# bOOST_cONVERTER_var_2.net
KiCad netlist of a schematic drawn in Altium Designer
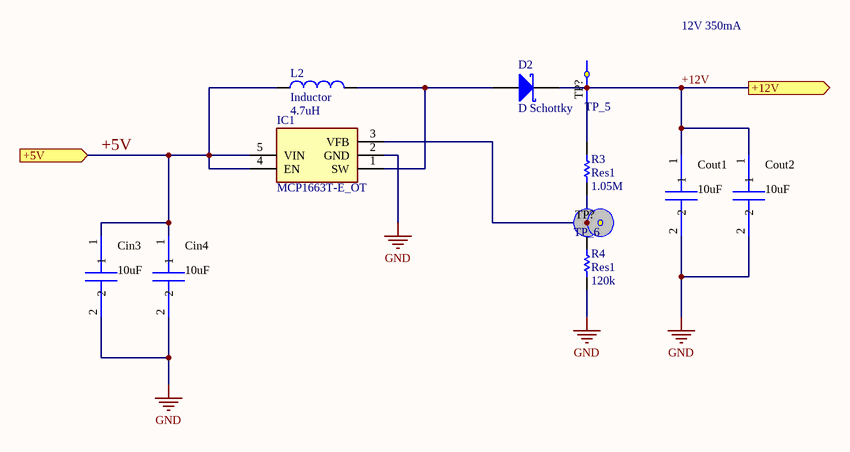
[diagram p0: bOOST cONVERTER_var 2.SchDoc]

(export (version "E")
  (design (tool "Eeschema 10.0.6"))
  (components
    (comp (ref "Cin3")
      (value "10uF")
      (description "C3216X6S1V106K16")
      (fields (field (name "MANUFACTURER PART NUMBER") "C3216X6S1V106K160AC"))
      (libsource (lib "TI WEBENCH") (part "Cin"))
    )
    (comp (ref "Cin4")
      (value "10uF")
      (description "C3216X6S1V106K16")
      (fields (field (name "MANUFACTURER PART NUMBER") "C3216X6S1V106K160AC"))
      (libsource (lib "TI WEBENCH") (part "Cin"))
    )
    (comp (ref "Cout1")
      (value "10uF")
      (description "C3216X6S1V106K16")
      (fields (field (name "MANUFACTURER PART NUMBER") "C3216X6S1V106K160AC"))
      (libsource (lib "TI WEBENCH") (part "Cin"))
    )
    (comp (ref "Cout2")
      (value "10uF")
      (description "C3216X6S1V106K16")
      (fields (field (name "MANUFACTURER PART NUMBER") "C3216X6S1V106K160AC"))
      (libsource (lib "TI WEBENCH") (part "Cin"))
    )
    (comp (ref "D2")
      (value "D Schottky")
      (footprint "SMB")
      (description "Schottky Diode")
      (fields (field (name "PUBLISHER") "Altium Limited"))
      (libsource (lib "Miscellaneous Devices") (part "D Schottky"))
    )
    (comp (ref "IC1")
      (value "MCP1663T-E_OT")
      (footprint "SamacSys:SOT95P270X145-5N")
      (description "Integrated Circuit")
      (fields
        (field (name "MANUFACTURER_PART_NUMBER") "MCP1663T-E/OT")
        (field (name "MOUSER PART NUMBER") "579-MCP1663T-E/OT")
      )
      (libsource (lib "*") (part "MCP1663T-E_OT"))
    )
    (comp (ref "L2")
      (value "Inductor")
      (footprint "0402-A")
      (fields (field (name "ALTIUM_VALUE") "4.7uH") (field (name "PUBLISHER") "Altium Limited"))
      (libsource (lib "Miscellaneous Devices") (part "Inductor"))
    )
    (comp (ref "R3")
      (value "Res1")
      (footprint "AXIAL-0.3")
      (description "Resistor")
      (fields (field (name "ALTIUM_VALUE") "1.05M") (field (name "PUBLISHER") "Altium Limited"))
      (libsource (lib "Miscellaneous Devices") (part "Res1"))
    )
    (comp (ref "R4")
      (value "Res1")
      (footprint "AXIAL-0.3")
      (description "Resistor")
      (fields (field (name "ALTIUM_VALUE") "120k") (field (name "PUBLISHER") "Altium Limited"))
      (libsource (lib "Miscellaneous Devices") (part "Res1"))
    )
    (comp (ref "TP_5")
      (value "Test_point")
      (footprint "PCBComponent_1")
      (description "Test_Point")
      (libsource (lib "") (part "Test_point_1"))
    )
    (comp (ref "TP_6")
      (value "Test_point")
      (footprint "PCBComponent_1")
      (description "Test_Point")
      (libsource (lib "Test_pointbun") (part "Test_point"))
    )
  )
  (nets
    (net (code "1") (name "/+5V") (class "Default")
      (node (ref "Cin3") (pin "1") (pinfunction "1_1") (pintype "passive"))
      (node (ref "Cin4") (pin "1") (pinfunction "1_1") (pintype "passive"))
      (node (ref "IC1") (pin "4") (pinfunction "EN_4") (pintype "passive"))
      (node (ref "IC1") (pin "5") (pinfunction "VIN_5") (pintype "passive"))
      (node (ref "L2") (pin "1") (pinfunction "1_1") (pintype "passive"))
    )
    (net (code "2") (name "/+12V") (class "Default")
      (node (ref "Cout1") (pin "1") (pinfunction "1_1") (pintype "passive"))
      (node (ref "Cout2") (pin "1") (pinfunction "1_1") (pintype "passive"))
      (node (ref "D2") (pin "2") (pinfunction "K_2") (pintype "passive"))
      (node (ref "R3") (pin "1") (pinfunction "1_1") (pintype "passive"))
      (node (ref "TP_5") (pin "TP?") (pinfunction "=value_TP?") (pintype "passive"))
    )
    (net (code "3") (name "GND") (class "Default")
      (node (ref "Cin3") (pin "2") (pinfunction "2_2") (pintype "passive"))
      (node (ref "Cin4") (pin "2") (pinfunction "2_2") (pintype "passive"))
      (node (ref "Cout1") (pin "2") (pinfunction "2_2") (pintype "passive"))
      (node (ref "Cout2") (pin "2") (pinfunction "2_2") (pintype "passive"))
      (node (ref "IC1") (pin "2") (pinfunction "GND_2") (pintype "passive"))
      (node (ref "R4") (pin "2") (pinfunction "2_2") (pintype "passive"))
    )
    (net (code "4") (name "Net-(D2-A)") (class "Default")
      (node (ref "D2") (pin "1") (pinfunction "A_1") (pintype "passive"))
      (node (ref "IC1") (pin "1") (pinfunction "SW_1") (pintype "passive"))
      (node (ref "L2") (pin "2") (pinfunction "2_2") (pintype "passive"))
    )
    (net (code "5") (name "Net-(IC1-VFB)") (class "Default")
      (node (ref "IC1") (pin "3") (pinfunction "VFB_3") (pintype "passive"))
      (node (ref "R3") (pin "2") (pinfunction "2_2") (pintype "passive"))
      (node (ref "R4") (pin "1") (pinfunction "1_1") (pintype "passive"))
      (node (ref "TP_6") (pin "TP?") (pinfunction "=value_TP?") (pintype "passive"))
    )
  )
)
